# SCH_Pompe_2022-04-02.net
KiCad netlist of a schematic drawn in EasyEDA
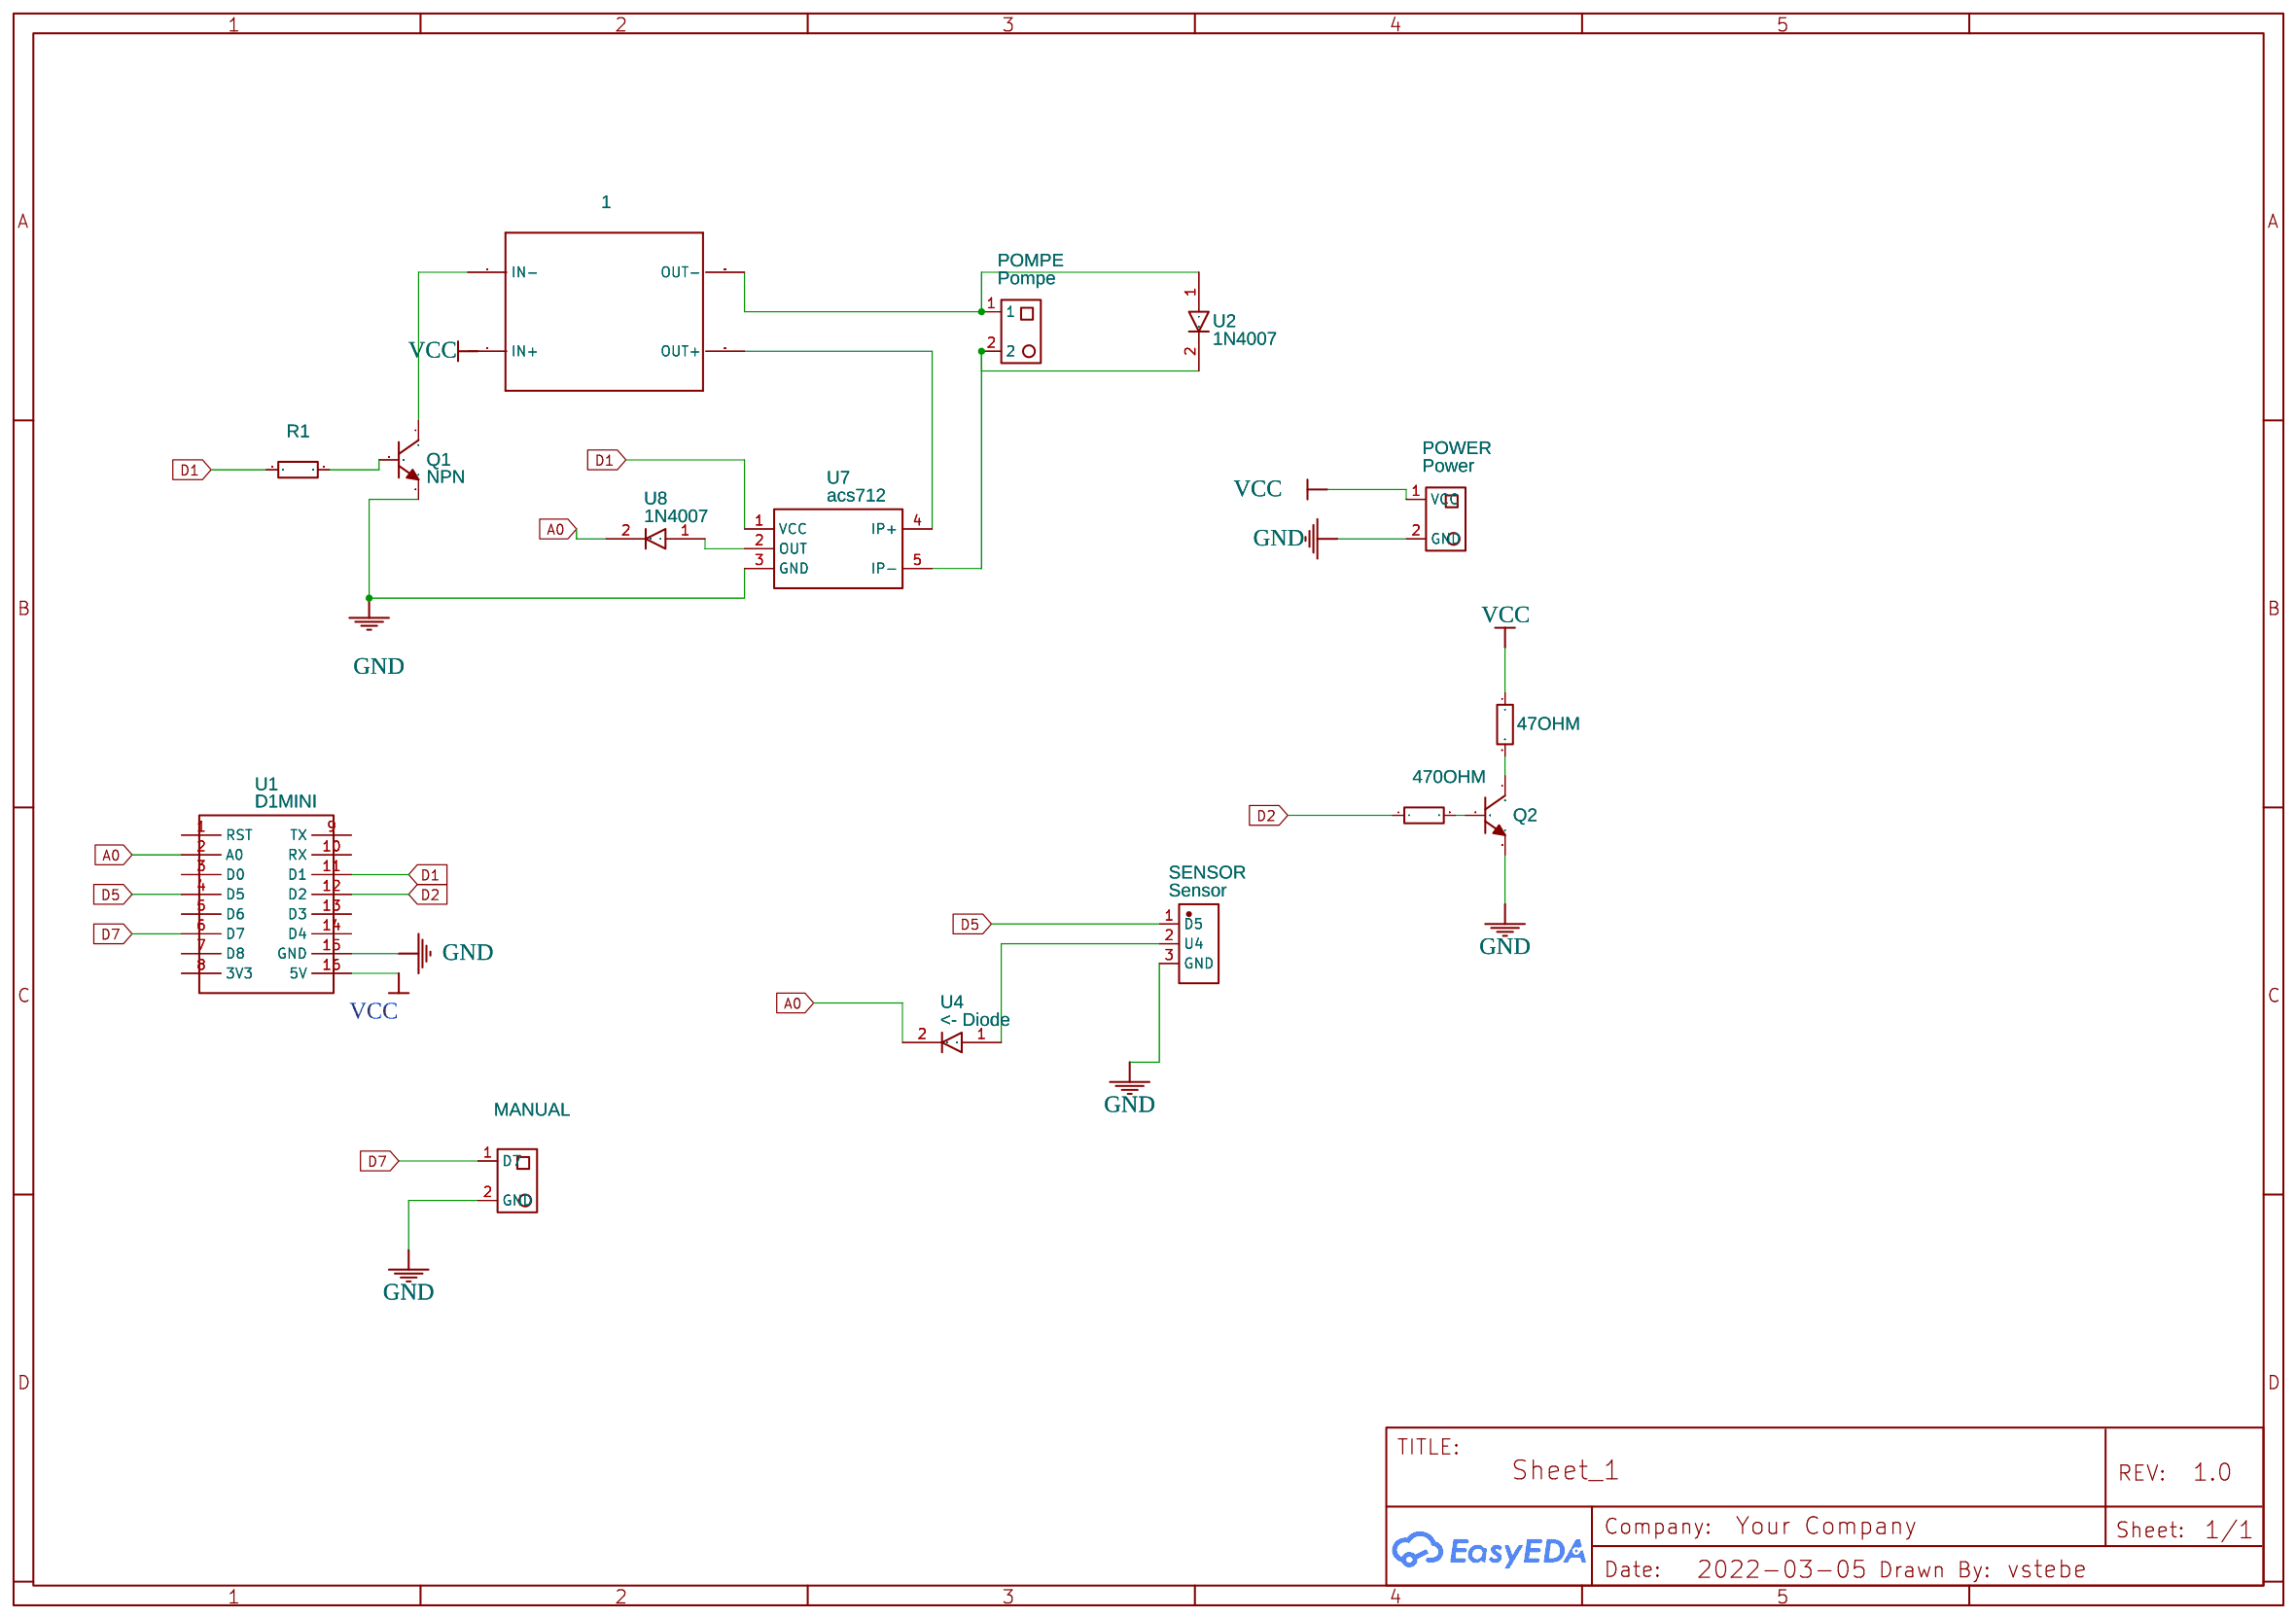
[diagram p0: schematic sheet]

(export (version "E")
  (design (tool "Eeschema 10.0.6"))
  (components
    (comp (ref "1") (value "DC-DC-STEP-UP-MT3608") (libsource (lib "") (part "DC-DC-STEP-UP-MT3608")))
    (comp (ref "47OHM")
      (value "ResistorToday")
      (fields
        (field (name "BOM_Manufacturer Part") "EWWR0001J20R0T9")
        (field (name "BOM_Supplier Part") "X16151710")
      )
      (libsource (lib "") (part "Resistor Normal_2"))
    )
    (comp (ref "470OHM")
      (value "ResistorToday")
      (fields
        (field (name "BOM_Manufacturer Part") "EWWR0001J20R0T9")
        (field (name "BOM_Supplier Part") "X16151710")
      )
      (libsource (lib "") (part "Resistor Normal_1"))
    )
    (comp (ref "MANUAL") (value "Manual") (libsource (lib "") (part "JST XH 2 PIN_2")))
    (comp (ref "POMPE") (value "Pompe") (libsource (lib "") (part "JST XH 2 PIN_1")))
    (comp (ref "POWER") (value "Power") (libsource (lib "") (part "JST XH 2 PIN")))
    (comp (ref "Q1")
      (value "NPN")
      (fields (field (name "BOM_Manufacturer Part") "2N2222A") (field (name "BOM_Supplier Part") "C358533"))
      (libsource (lib "") (part "2N2222A FACILE_A_souder"))
    )
    (comp (ref "Q2")
      (value "2N2222A FACILE_A_souder")
      (fields (field (name "BOM_Manufacturer Part") "2N2222A") (field (name "BOM_Supplier Part") "C358533"))
      (libsource (lib "") (part "2N2222A FACILE_A_souder"))
    )
    (comp (ref "R1")
      (value "ResistorToday")
      (fields
        (field (name "BOM_Manufacturer Part") "EWWR0001J20R0T9")
        (field (name "BOM_Supplier Part") "X16151710")
      )
      (libsource (lib "") (part "Resistor Normal"))
    )
    (comp (ref "SENSOR")
      (value "Sensor")
      (fields
        (field (name "BOM_Manufacturer Part") "JST3-2.5T-1-3A")
        (field (name "BOM_Supplier Part") "C9900006101")
      )
      (libsource (lib "") (part "JST3-2.5T-1-3A"))
    )
    (comp (ref "U1") (value "D1MINI") (libsource (lib "") (part "D1MINI")))
    (comp (ref "U2") (value "1N4007") (libsource (lib "") (part "1N4007")))
    (comp (ref "U4") (value "<- Diode") (libsource (lib "") (part "1N4007_1")))
    (comp (ref "U7") (value "acs712") (libsource (lib "") (part "acs712")))
    (comp (ref "U8") (value "1N4007") (libsource (lib "") (part "1N4007_1")))
  )
  (nets
    (net (code "1") (name "A0") (class "Default")
      (node (ref "U1") (pin "2") (pinfunction "A0_2") (pintype "unspecified"))
      (node (ref "U4") (pin "2") (pinfunction "2_2") (pintype "unspecified"))
      (node (ref "U8") (pin "2") (pinfunction "2_2") (pintype "unspecified"))
    )
    (net (code "2") (name "D1") (class "Default")
      (node (ref "R1") (pin "1") (pinfunction "1_1") (pintype "unspecified"))
      (node (ref "U1") (pin "11") (pinfunction "D1_11") (pintype "unspecified"))
      (node (ref "U7") (pin "1") (pinfunction "VCC_1") (pintype "passive"))
    )
    (net (code "3") (name "D2") (class "Default")
      (node (ref "470OHM") (pin "1") (pinfunction "1_1") (pintype "unspecified"))
      (node (ref "U1") (pin "12") (pinfunction "D2_12") (pintype "unspecified"))
    )
    (net (code "4") (name "D5") (class "Default")
      (node (ref "SENSOR") (pin "1") (pinfunction "D5_1") (pintype "unspecified"))
      (node (ref "U1") (pin "4") (pinfunction "D5_4") (pintype "unspecified"))
    )
    (net (code "5") (name "D7") (class "Default")
      (node (ref "MANUAL") (pin "1") (pinfunction "D7_1") (pintype "unspecified"))
      (node (ref "U1") (pin "6") (pinfunction "D7_6") (pintype "unspecified"))
    )
    (net (code "6") (name "GND") (class "Default")
      (node (ref "MANUAL") (pin "2") (pinfunction "GND_2") (pintype "unspecified"))
      (node (ref "POWER") (pin "2") (pinfunction "GND_2") (pintype "unspecified"))
      (node (ref "Q1") (pin "3") (pinfunction "E_3") (pintype "unspecified"))
      (node (ref "Q2") (pin "3") (pinfunction "E_3") (pintype "unspecified"))
      (node (ref "SENSOR") (pin "3") (pinfunction "GND_3") (pintype "unspecified"))
      (node (ref "U1") (pin "15") (pinfunction "GND_15") (pintype "unspecified"))
      (node (ref "U7") (pin "3") (pinfunction "GND_3") (pintype "passive"))
    )
    (net (code "7") (name "Net-(1-PadOUT-)") (class "Default")
      (node (ref "1") (pin "OUT-") (pinfunction "OUT-_OUT-") (pintype "bidirectional"))
      (node (ref "POMPE") (pin "1") (pinfunction "1_1") (pintype "unspecified"))
      (node (ref "U2") (pin "1") (pinfunction "1_1") (pintype "unspecified"))
    )
    (net (code "8") (name "Net-(Q1-B)") (class "Default")
      (node (ref "Q1") (pin "2") (pinfunction "B_2") (pintype "unspecified"))
      (node (ref "R1") (pin "2") (pinfunction "2_2") (pintype "unspecified"))
    )
    (net (code "9") (name "Net-(Q1-C)") (class "Default")
      (node (ref "1") (pin "IN-") (pinfunction "IN-_IN-") (pintype "bidirectional"))
      (node (ref "Q1") (pin "1") (pinfunction "C_1") (pintype "unspecified"))
    )
    (net (code "10") (name "Net-(Q2-B)") (class "Default")
      (node (ref "470OHM") (pin "2") (pinfunction "2_2") (pintype "unspecified"))
      (node (ref "Q2") (pin "2") (pinfunction "B_2") (pintype "unspecified"))
    )
    (net (code "11") (name "Net-(Q2-C)") (class "Default")
      (node (ref "47OHM") (pin "2") (pinfunction "2_2") (pintype "unspecified"))
      (node (ref "Q2") (pin "1") (pinfunction "C_1") (pintype "unspecified"))
    )
    (net (code "12") (name "Net-(SENSOR-U4)") (class "Default")
      (node (ref "SENSOR") (pin "2") (pinfunction "U4_2") (pintype "unspecified"))
      (node (ref "U4") (pin "1") (pinfunction "1_1") (pintype "unspecified"))
    )
    (net (code "13") (name "Net-(U7-IP+)") (class "Default")
      (node (ref "1") (pin "OUT+") (pinfunction "OUT+_OUT+") (pintype "bidirectional"))
      (node (ref "U7") (pin "4") (pinfunction "IP+_4") (pintype "unspecified"))
    )
    (net (code "14") (name "Net-(U7-IP-)") (class "Default")
      (node (ref "POMPE") (pin "2") (pinfunction "2_2") (pintype "unspecified"))
      (node (ref "U2") (pin "2") (pinfunction "2_2") (pintype "unspecified"))
      (node (ref "U7") (pin "5") (pinfunction "IP-_5") (pintype "input"))
    )
    (net (code "15") (name "Net-(U7-OUT)") (class "Default")
      (node (ref "U7") (pin "2") (pinfunction "OUT_2") (pintype "output"))
      (node (ref "U8") (pin "1") (pinfunction "1_1") (pintype "unspecified"))
    )
    (net (code "16") (name "VCC") (class "Default")
      (node (ref "1") (pin "IN+") (pinfunction "IN+_IN+") (pintype "bidirectional"))
      (node (ref "47OHM") (pin "1") (pinfunction "1_1") (pintype "unspecified"))
      (node (ref "POWER") (pin "1") (pinfunction "VCC_1") (pintype "unspecified"))
      (node (ref "U1") (pin "16") (pinfunction "5V_16") (pintype "unspecified"))
    )
    (net (code "17") (name "unconnected-(U1-3V3-Pad8)") (class "Default")
      (node (ref "U1") (pin "8") (pinfunction "3V3_8") (pintype "unspecified"))
    )
    (net (code "18") (name "unconnected-(U1-D0-Pad3)") (class "Default")
      (node (ref "U1") (pin "3") (pinfunction "D0_3") (pintype "unspecified"))
    )
    (net (code "19") (name "unconnected-(U1-D3-Pad13)") (class "Default")
      (node (ref "U1") (pin "13") (pinfunction "D3_13") (pintype "unspecified"))
    )
    (net (code "20") (name "unconnected-(U1-D4-Pad14)") (class "Default")
      (node (ref "U1") (pin "14") (pinfunction "D4_14") (pintype "unspecified"))
    )
    (net (code "21") (name "unconnected-(U1-D6-Pad5)") (class "Default")
      (node (ref "U1") (pin "5") (pinfunction "D6_5") (pintype "unspecified"))
    )
    (net (code "22") (name "unconnected-(U1-D8-Pad7)") (class "Default")
      (node (ref "U1") (pin "7") (pinfunction "D8_7") (pintype "unspecified"))
    )
    (net (code "23") (name "unconnected-(U1-RST-Pad1)") (class "Default")
      (node (ref "U1") (pin "1") (pinfunction "RST_1") (pintype "unspecified"))
    )
    (net (code "24") (name "unconnected-(U1-RX-Pad10)") (class "Default")
      (node (ref "U1") (pin "10") (pinfunction "RX_10") (pintype "unspecified"))
    )
    (net (code "25") (name "unconnected-(U1-TX-Pad9)") (class "Default")
      (node (ref "U1") (pin "9") (pinfunction "TX_9") (pintype "unspecified"))
    )
  )
)
